# L293D.net
KiCad netlist of a schematic drawn in EAGLE
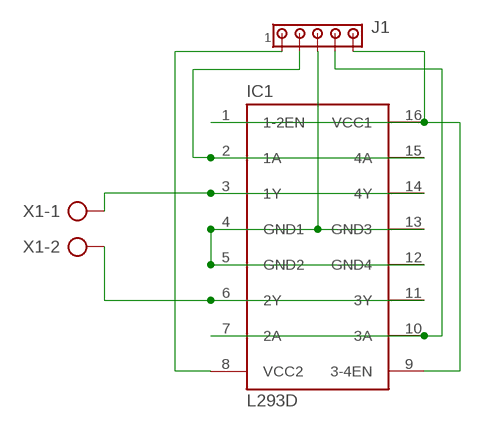
[diagram p0: schematic, sheet 1]

(export (version "E")
  (design (tool "Eeschema 10.0.6"))
  (components
    (comp (ref "IC1")
      (value "L293D")
      (footprint "eagle-import:DIL16")
      (libsource (lib "eagle-import") (part "L293D"))
    )
    (comp (ref "J1")
      (value "MTA05-100")
      (footprint "eagle-import:10X05MTA")
      (libsource (lib "eagle-import") (part "MTA05-100"))
    )
    (comp (ref "X1")
      (value "AK300/2")
      (footprint "eagle-import:AK300_2")
      (libsource (lib "eagle-import") (part "AK300/2"))
    )
  )
  (nets
    (net (code "1") (name "Net-(IC1-1-2EN)") (class "Default")
      (node (ref "IC1") (pin "1") (pinfunction "1-2EN_1") (pintype "input"))
      (node (ref "IC1") (pin "16") (pinfunction "VCC1_16") (pintype "power_in"))
      (node (ref "IC1") (pin "9") (pinfunction "3-4EN_9") (pintype "input"))
      (node (ref "J1") (pin "5") (pinfunction "5_5") (pintype "passive"))
    )
    (net (code "2") (name "Net-(IC1-1A)") (class "Default")
      (node (ref "IC1") (pin "15") (pinfunction "4A_15") (pintype "input"))
      (node (ref "IC1") (pin "2") (pinfunction "1A_2") (pintype "input"))
      (node (ref "J1") (pin "2") (pinfunction "2_2") (pintype "passive"))
    )
    (net (code "3") (name "Net-(IC1-1Y)") (class "Default")
      (node (ref "IC1") (pin "14") (pinfunction "4Y_14") (pintype "output"))
      (node (ref "IC1") (pin "3") (pinfunction "1Y_3") (pintype "output"))
      (node (ref "X1") (pin "1") (pinfunction "KL_1") (pintype "passive"))
    )
    (net (code "4") (name "Net-(IC1-2A)") (class "Default")
      (node (ref "IC1") (pin "10") (pinfunction "3A_10") (pintype "input"))
      (node (ref "IC1") (pin "7") (pinfunction "2A_7") (pintype "input"))
      (node (ref "J1") (pin "4") (pinfunction "4_4") (pintype "passive"))
    )
    (net (code "5") (name "Net-(IC1-2Y)") (class "Default")
      (node (ref "IC1") (pin "11") (pinfunction "3Y_11") (pintype "output"))
      (node (ref "IC1") (pin "6") (pinfunction "2Y_6") (pintype "output"))
      (node (ref "X1") (pin "2") (pinfunction "KL_2") (pintype "passive"))
    )
    (net (code "6") (name "Net-(IC1-GND1)") (class "Default")
      (node (ref "IC1") (pin "12") (pinfunction "GND4_12") (pintype "power_in"))
      (node (ref "IC1") (pin "13") (pinfunction "GND3_13") (pintype "power_in"))
      (node (ref "IC1") (pin "4") (pinfunction "GND1_4") (pintype "power_in"))
      (node (ref "IC1") (pin "5") (pinfunction "GND2_5") (pintype "power_in"))
      (node (ref "J1") (pin "3") (pinfunction "3_3") (pintype "passive"))
    )
    (net (code "7") (name "Net-(IC1-VCC2)") (class "Default")
      (node (ref "IC1") (pin "8") (pinfunction "VCC2_8") (pintype "power_in"))
      (node (ref "J1") (pin "1") (pinfunction "1_1") (pintype "passive"))
    )
  )
)
